# SAMV71_Xplained_Ultra_EDBG.net
KiCad netlist of a schematic drawn in Altium Designer
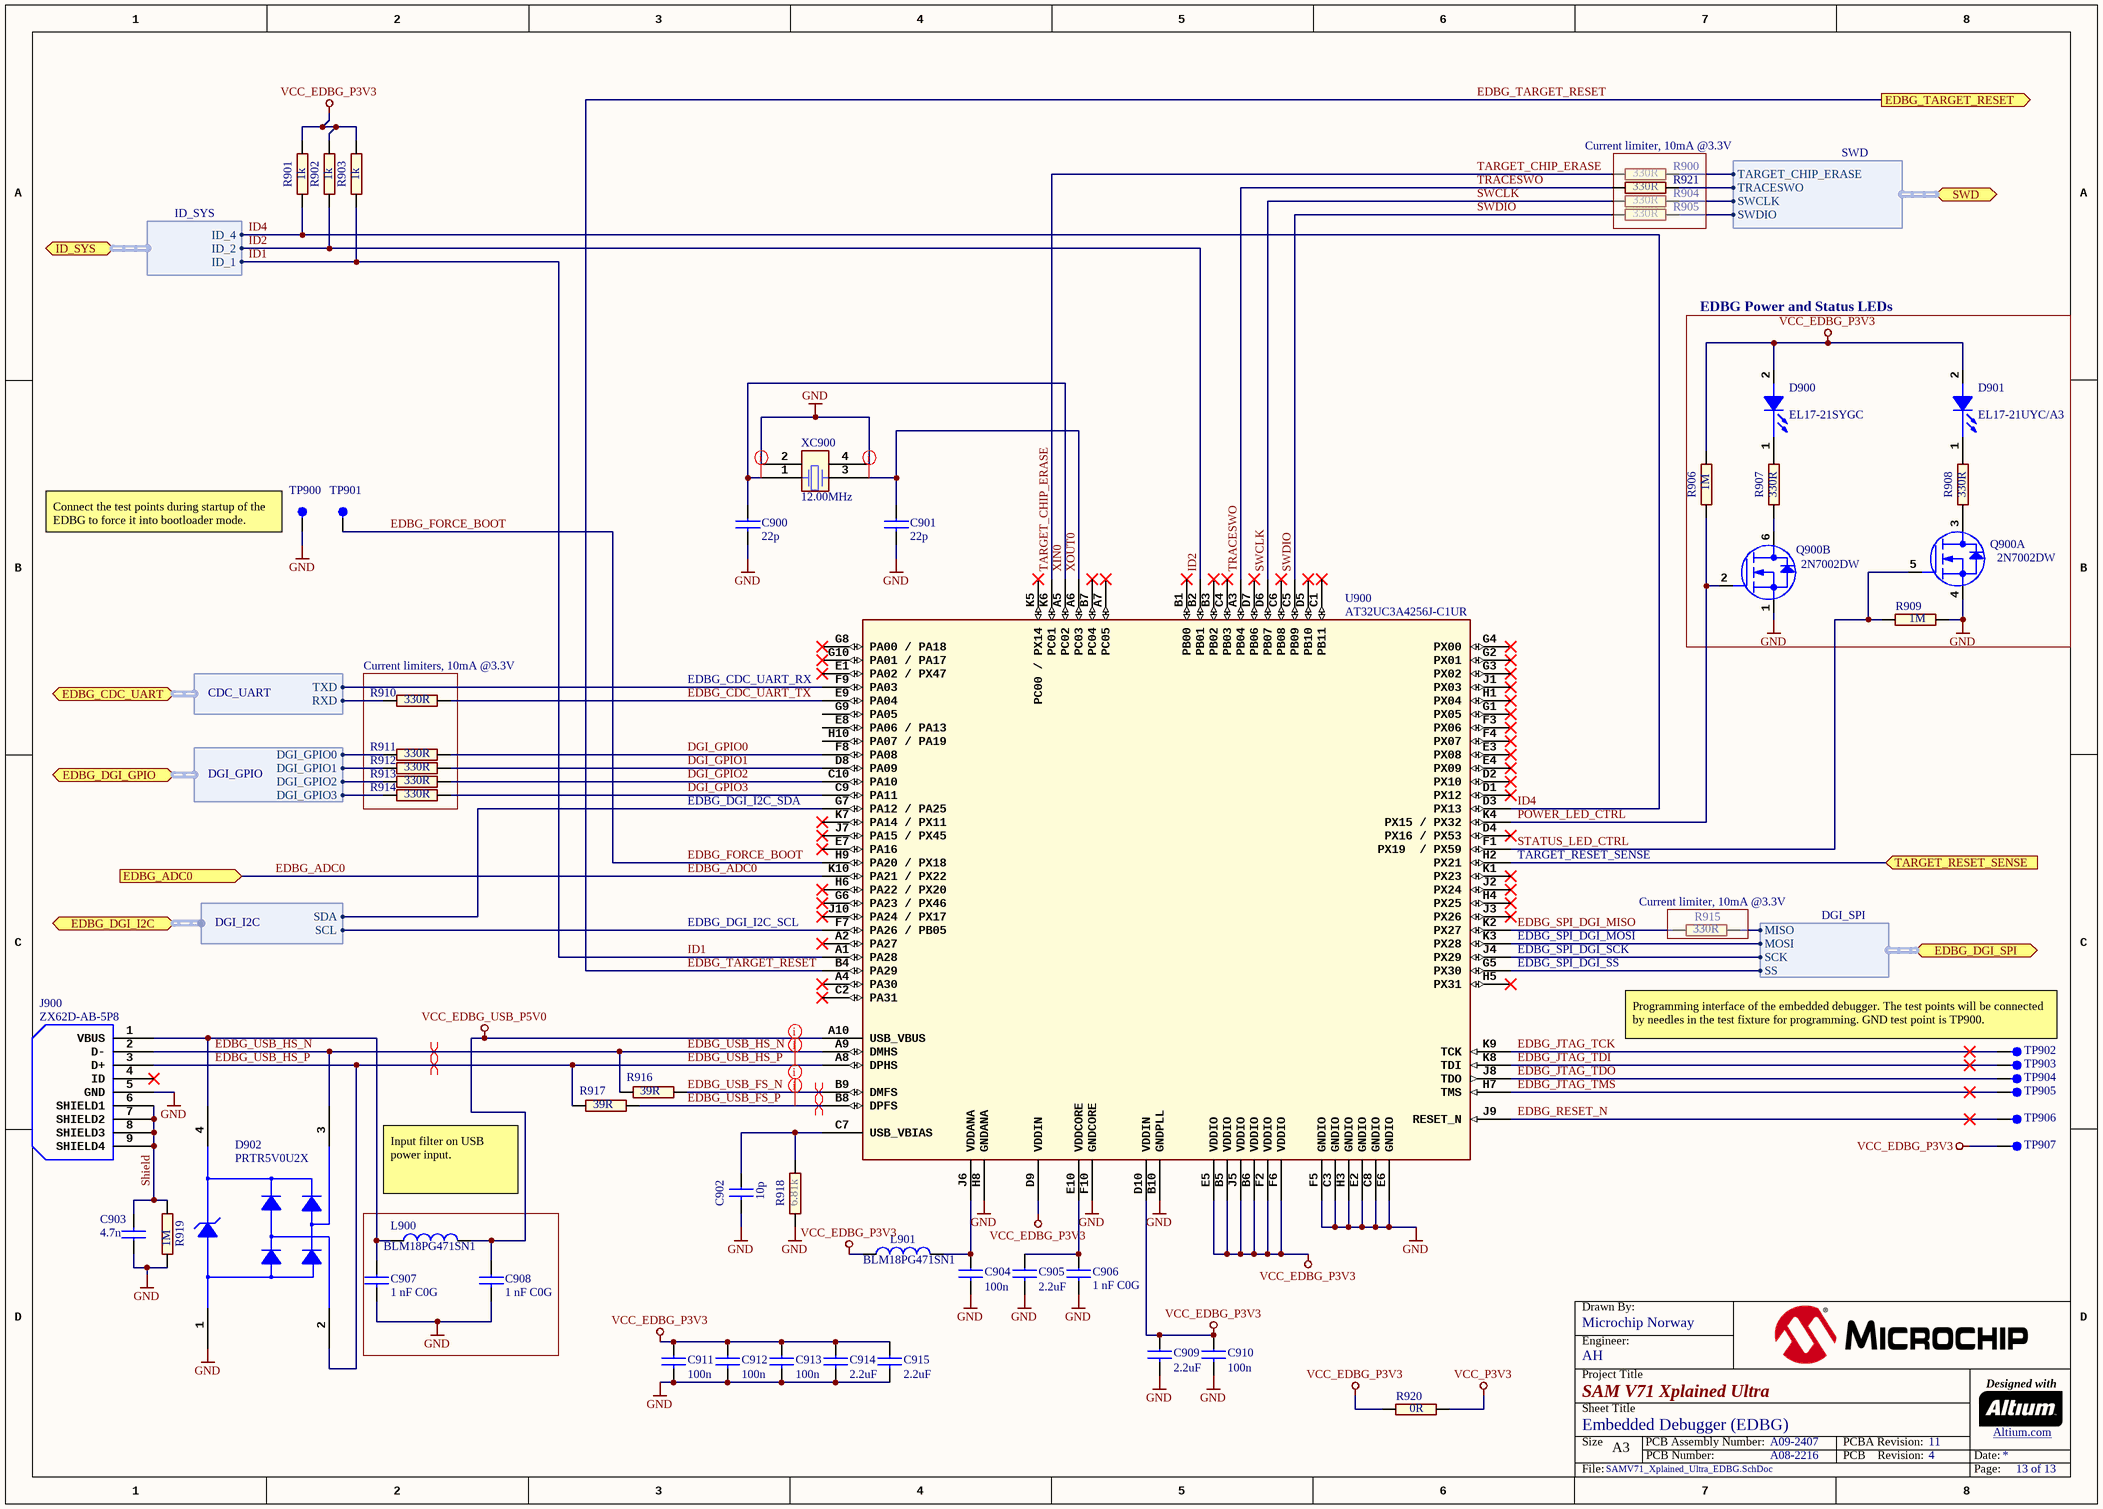
[diagram p0: SAMV71_Xplained_Ultra_EDBG.SchDoc]

(export (version "E")
  (design (tool "Eeschema 10.0.6"))
  (components
    (comp (ref "C900")
      (value "22p")
      (footprint "AP1-00053")
      (description "Ceramic capacitor, SMD 0402, NP0, 50V, +/-5%")
      (fields (field (name "TOLERANCE") "50V, +/-5%") (field (name "MANUFACTURER") "YAGEO CORP"))
      (libsource (lib "AltiumDbLib") (part "CAP-NONPOL"))
    )
    (comp (ref "C901")
      (value "22p")
      (footprint "AP1-00053")
      (description "Ceramic capacitor, SMD 0402, NP0, 50V, +/-5%")
      (fields (field (name "TOLERANCE") "50V, +/-5%") (field (name "MANUFACTURER") "YAGEO CORP"))
      (libsource (lib "AltiumDbLib") (part "CAP-NONPOL"))
    )
    (comp (ref "C902")
      (value "10p")
      (footprint "AP1-00053")
      (description "Ceramic capacitor, SMD 0402, NP0, 50V, +/-5%")
      (fields (field (name "TOLERANCE") "50V, +/-5%") (field (name "MANUFACTURER") "AVX"))
      (libsource (lib "AltiumDbLib") (part "CAP-NONPOL"))
    )
    (comp (ref "C903")
      (value "4.7n")
      (footprint "AP1-00053")
      (description "Ceramic capacitor, SMD 0402, X7R, 25V, +/-10%")
      (fields (field (name "TOLERANCE") "25V, +/-10%") (field (name "MANUFACTURER") "PHYCOMP"))
      (libsource (lib "AltiumDbLib") (part "CAP-NONPOL"))
    )
    (comp (ref "C904")
      (value "100n")
      (footprint "AP1-00053")
      (description "Ceramic capacitor, SMD 0402, X7R, 16V, +/-10%")
      (fields (field (name "TOLERANCE") "16V, +/-10%") (field (name "MANUFACTURER") "Kemet"))
      (libsource (lib "AltiumDbLib") (part "CAP-NONPOL"))
    )
    (comp (ref "C905")
      (value "2.2uF")
      (footprint "AP1-00053")
      (description "Ceramic capacitor, SMD 0402, X5R, 6.3V, +/-20%")
      (fields (field (name "TOLERANCE") "Â±20%") (field (name "MANUFACTURER") "Kemet"))
      (libsource (lib "AltiumDbLib") (part "CAP-NONPOL"))
    )
    (comp (ref "C906")
      (value "1 nF C0G")
      (footprint "AP1-00053")
      (description "Ceramic capacitor, SMD 0402, C0G, 50V, +/-5%")
      (fields (field (name "TOLERANCE") "5%") (field (name "MANUFACTURER") "Murata"))
      (libsource (lib "AltiumDbLib") (part "CAP-NONPOL"))
    )
    (comp (ref "C907")
      (value "1 nF C0G")
      (footprint "AP1-00053")
      (description "Ceramic capacitor, SMD 0402, C0G, 50V, +/-5%")
      (fields (field (name "TOLERANCE") "5%") (field (name "MANUFACTURER") "Murata"))
      (libsource (lib "AltiumDbLib") (part "CAP-NONPOL"))
    )
    (comp (ref "C908")
      (value "1 nF C0G")
      (footprint "AP1-00053")
      (description "Ceramic capacitor, SMD 0402, C0G, 50V, +/-5%")
      (fields (field (name "TOLERANCE") "5%") (field (name "MANUFACTURER") "Murata"))
      (libsource (lib "AltiumDbLib") (part "CAP-NONPOL"))
    )
    (comp (ref "C909")
      (value "2.2uF")
      (footprint "AP1-00053")
      (description "Ceramic capacitor, SMD 0402, X5R, 6.3V, +/-20%")
      (fields (field (name "TOLERANCE") "Â±20%") (field (name "MANUFACTURER") "Kemet"))
      (libsource (lib "AltiumDbLib") (part "CAP-NONPOL"))
    )
    (comp (ref "C910")
      (value "100n")
      (footprint "AP1-00053")
      (description "Ceramic capacitor, SMD 0402, X7R, 16V, +/-10%")
      (fields (field (name "TOLERANCE") "16V, +/-10%") (field (name "MANUFACTURER") "Kemet"))
      (libsource (lib "AltiumDbLib") (part "CAP-NONPOL"))
    )
    (comp (ref "C911")
      (value "100n")
      (footprint "AP1-00053")
      (description "Ceramic capacitor, SMD 0402, X7R, 16V, +/-10%")
      (fields (field (name "TOLERANCE") "16V, +/-10%") (field (name "MANUFACTURER") "Kemet"))
      (libsource (lib "AltiumDbLib") (part "CAP-NONPOL"))
    )
    (comp (ref "C912")
      (value "100n")
      (footprint "AP1-00053")
      (description "Ceramic capacitor, SMD 0402, X7R, 16V, +/-10%")
      (fields (field (name "TOLERANCE") "16V, +/-10%") (field (name "MANUFACTURER") "Kemet"))
      (libsource (lib "AltiumDbLib") (part "CAP-NONPOL"))
    )
    (comp (ref "C913")
      (value "100n")
      (footprint "AP1-00053")
      (description "Ceramic capacitor, SMD 0402, X7R, 16V, +/-10%")
      (fields (field (name "TOLERANCE") "16V, +/-10%") (field (name "MANUFACTURER") "Kemet"))
      (libsource (lib "AltiumDbLib") (part "CAP-NONPOL"))
    )
    (comp (ref "C914")
      (value "2.2uF")
      (footprint "AP1-00053")
      (description "Ceramic capacitor, SMD 0402, X5R, 6.3V, +/-20%")
      (fields (field (name "TOLERANCE") "Â±20%") (field (name "MANUFACTURER") "Kemet"))
      (libsource (lib "AltiumDbLib") (part "CAP-NONPOL"))
    )
    (comp (ref "C915")
      (value "2.2uF")
      (footprint "AP1-00053")
      (description "Ceramic capacitor, SMD 0402, X5R, 6.3V, +/-20%")
      (fields (field (name "TOLERANCE") "Â±20%") (field (name "MANUFACTURER") "Kemet"))
      (libsource (lib "AltiumDbLib") (part "CAP-NONPOL"))
    )
    (comp (ref "D900")
      (value "EL17-21SYGC")
      (footprint "AP4-00013")
      (description "LED, Green, Wave length=575nm, SMD 0805, ±70°")
      (fields (field (name "MANUFACTURER") "Everlight"))
      (libsource (lib "AltiumDbLib") (part "LED_12"))
    )
    (comp (ref "D901")
      (value "EL17-21UYC/A3")
      (footprint "AP4-00013")
      (description "LED, Yellow, Wave length=591nm, SMD 0805, ±70°")
      (fields (field (name "MANUFACTURER") "Everlight") (field (name "MPN") "17-21UYC/S530-A3/TR8"))
      (libsource (lib "AltiumDbLib") (part "LED_12"))
    )
    (comp (ref "D902")
      (value "PRTR5V0U2X")
      (footprint "AP4-00001")
      (description "Double rail-to-rail USB ESD protection diode")
      (fields (field (name "MANUFACTURER") "NXP"))
      (libsource (lib "AltiumDbLib") (part "PRTR5V0U2X"))
    )
    (comp (ref "J900")
      (value "ZX62D-AB-5P8")
      (footprint "AP8-00852")
      (description "Micro USB AB Connector, Standard SMT + DIP")
      (fields (field (name "MANUFACTURER") "HIROSE") (field (name "MPN") "ZX62D-AB-5P8(30)"))
      (libsource (lib "AltiumDbLib") (part "USB_AB"))
    )
    (comp (ref "L900")
      (value "BLM18PG471SN1")
      (footprint "AP3-00005")
      (description "SMD RF inductor 0603. Z=470Ohm (@100MHz), Max R(dc)=0.65Ohm, Max current=1A")
      (fields (field (name "MANUFACTURER") "Murata"))
      (libsource (lib "AltiumDbLib") (part "INDUCTOR"))
    )
    (comp (ref "L901")
      (value "BLM18PG471SN1")
      (footprint "AP3-00005")
      (description "SMD RF inductor 0603. Z=470Ohm (@100MHz), Max R(dc)=0.65Ohm, Max current=1A")
      (fields (field (name "MANUFACTURER") "Murata"))
      (libsource (lib "AltiumDbLib") (part "INDUCTOR"))
    )
    (comp (ref "Q900")
      (value "2N7002DW")
      (footprint "AP5-00001")
      (description "Dual N-Channel MOSFET, 60V, 115mA cont,RDS(ON) < 7.5 Ohm @50mA@5V, SOT-363")
      (fields (field (name "MANUFACTURER") "Fairchild"))
      (libsource (lib "AltiumDbLib") (part "MOSFET_DUAL_N_S2G2D1S1G1D2"))
    )
    (comp (ref "R900")
      (value "330R")
      (footprint "AP2-00000")
      (description "Thick film resistor, SMD 0402, 1/16W, 1%")
      (fields (field (name "TOLERANCE") "1 %") (field (name "MANUFACTURER") "ASJ"))
      (libsource (lib "") (part "R2_1"))
    )
    (comp (ref "R901")
      (value "1k")
      (footprint "AP2-00000")
      (description "Thick film resistor, SMD 0402, 1/16W, 1%")
      (fields (field (name "TOLERANCE") "1 %") (field (name "MANUFACTURER") "ASJ"))
      (libsource (lib "AltiumDbLib") (part "R2"))
    )
    (comp (ref "R902")
      (value "1k")
      (footprint "AP2-00000")
      (description "Thick film resistor, SMD 0402, 1/16W, 1%")
      (fields (field (name "TOLERANCE") "1 %") (field (name "MANUFACTURER") "ASJ"))
      (libsource (lib "AltiumDbLib") (part "R2"))
    )
    (comp (ref "R903")
      (value "1k")
      (footprint "AP2-00000")
      (description "Thick film resistor, SMD 0402, 1/16W, 1%")
      (fields (field (name "TOLERANCE") "1 %") (field (name "MANUFACTURER") "ASJ"))
      (libsource (lib "AltiumDbLib") (part "R2"))
    )
    (comp (ref "R904")
      (value "330R")
      (footprint "AP2-00000")
      (description "Thick film resistor, SMD 0402, 1/16W, 1%")
      (fields (field (name "TOLERANCE") "1 %") (field (name "MANUFACTURER") "ASJ"))
      (libsource (lib "") (part "R2_1"))
    )
    (comp (ref "R905")
      (value "330R")
      (footprint "AP2-00000")
      (description "Thick film resistor, SMD 0402, 1/16W, 1%")
      (fields (field (name "TOLERANCE") "1 %") (field (name "MANUFACTURER") "ASJ"))
      (libsource (lib "") (part "R2_1"))
    )
    (comp (ref "R906")
      (value "1M")
      (footprint "AP2-00000")
      (description "Thick film resistor, SMD 0402, 1/16W, 1%")
      (fields (field (name "TOLERANCE") "1 %") (field (name "MANUFACTURER") "ASJ"))
      (libsource (lib "AltiumDbLib") (part "R2"))
    )
    (comp (ref "R907")
      (value "330R")
      (footprint "AP2-00000")
      (description "Thick film resistor, SMD 0402, 1/16W, 1%")
      (fields (field (name "TOLERANCE") "1 %") (field (name "MANUFACTURER") "ASJ"))
      (libsource (lib "AltiumDbLib") (part "R2"))
    )
    (comp (ref "R908")
      (value "330R")
      (footprint "AP2-00000")
      (description "Thick film resistor, SMD 0402, 1/16W, 1%")
      (fields (field (name "TOLERANCE") "1 %") (field (name "MANUFACTURER") "ASJ"))
      (libsource (lib "AltiumDbLib") (part "R2"))
    )
    (comp (ref "R909")
      (value "1M")
      (footprint "AP2-00000")
      (description "Thick film resistor, SMD 0402, 1/16W, 1%")
      (fields (field (name "TOLERANCE") "1 %") (field (name "MANUFACTURER") "ASJ"))
      (libsource (lib "") (part "R2_3"))
    )
    (comp (ref "R910")
      (value "330R")
      (footprint "AP2-00000")
      (description "Thick film resistor, SMD 0402, 1/16W, 1%")
      (fields (field (name "TOLERANCE") "1 %") (field (name "MANUFACTURER") "ASJ"))
      (libsource (lib "") (part "R2_1"))
    )
    (comp (ref "R911")
      (value "330R")
      (footprint "AP2-00000")
      (description "Thick film resistor, SMD 0402, 1/16W, 1%")
      (fields (field (name "TOLERANCE") "1 %") (field (name "MANUFACTURER") "ASJ"))
      (libsource (lib "") (part "R2_1"))
    )
    (comp (ref "R912")
      (value "330R")
      (footprint "AP2-00000")
      (description "Thick film resistor, SMD 0402, 1/16W, 1%")
      (fields (field (name "TOLERANCE") "1 %") (field (name "MANUFACTURER") "ASJ"))
      (libsource (lib "") (part "R2_1"))
    )
    (comp (ref "R913")
      (value "330R")
      (footprint "AP2-00000")
      (description "Thick film resistor, SMD 0402, 1/16W, 1%")
      (fields (field (name "TOLERANCE") "1 %") (field (name "MANUFACTURER") "ASJ"))
      (libsource (lib "") (part "R2_1"))
    )
    (comp (ref "R914")
      (value "330R")
      (footprint "AP2-00000")
      (description "Thick film resistor, SMD 0402, 1/16W, 1%")
      (fields (field (name "TOLERANCE") "1 %") (field (name "MANUFACTURER") "ASJ"))
      (libsource (lib "") (part "R2_1"))
    )
    (comp (ref "R915")
      (value "330R")
      (footprint "AP2-00000")
      (description "Thick film resistor, SMD 0402, 1/16W, 1%")
      (fields (field (name "TOLERANCE") "1 %") (field (name "MANUFACTURER") "ASJ"))
      (libsource (lib "") (part "R2_1"))
    )
    (comp (ref "R916")
      (value "39R")
      (footprint "AP2-00011")
      (description "Thick film resistor, SMD 0402, 1/16W, 1%")
      (fields (field (name "TOLERANCE") "1 %") (field (name "MANUFACTURER") "ASJ"))
      (libsource (lib "") (part "R2_2"))
    )
    (comp (ref "R917")
      (value "39R")
      (footprint "AP2-00011")
      (description "Thick film resistor, SMD 0402, 1/16W, 1%")
      (fields (field (name "TOLERANCE") "1 %") (field (name "MANUFACTURER") "ASJ"))
      (libsource (lib "") (part "R2_2"))
    )
    (comp (ref "R918")
      (value "6.81k")
      (footprint "AP2-00011")
      (description "Thick film resistor, SMD 0402, 1/16W, 1%")
      (fields (field (name "TOLERANCE") "1%") (field (name "MANUFACTURER") "vishay"))
      (libsource (lib "AltiumDbLib") (part "R2"))
    )
    (comp (ref "R919")
      (value "1M")
      (footprint "AP2-00011")
      (description "Thick film resistor, SMD 0402, 1/16W, 1%")
      (fields (field (name "TOLERANCE") "1 %") (field (name "MANUFACTURER") "ASJ"))
      (libsource (lib "") (part "R2_4"))
    )
    (comp (ref "R920")
      (value "0R")
      (footprint "AP2-00000")
      (description "Thick film resistor, SMD 0402, 1/16W, 1%")
      (fields (field (name "TOLERANCE") "1 %") (field (name "MANUFACTURER") "(n/a)"))
      (libsource (lib "") (part "R2_1"))
    )
    (comp (ref "R921")
      (value "330R")
      (footprint "AP2-00000")
      (description "Thick film resistor, SMD 0402, 1/16W, 1%")
      (fields (field (name "TOLERANCE") "1 %") (field (name "MANUFACTURER") "ASJ"))
      (libsource (lib "") (part "R2_1"))
    )
    (comp (ref "TP900")
      (value "~")
      (footprint "AP8-00010")
      (description "Single SMD testpad")
      (libsource (lib "AltiumDbLib") (part "TESTPOINT"))
    )
    (comp (ref "TP901")
      (value "~")
      (footprint "AP8-00010")
      (description "Single SMD testpad")
      (libsource (lib "AltiumDbLib") (part "TESTPOINT"))
    )
    (comp (ref "TP902")
      (value "~")
      (footprint "AP8-00010")
      (description "Single SMD testpad")
      (libsource (lib "AltiumDbLib") (part "TESTPOINT"))
    )
    (comp (ref "TP903")
      (value "~")
      (footprint "AP8-00010")
      (description "Single SMD testpad")
      (libsource (lib "AltiumDbLib") (part "TESTPOINT"))
    )
    (comp (ref "TP904")
      (value "~")
      (footprint "AP8-00010")
      (description "Single SMD testpad")
      (libsource (lib "AltiumDbLib") (part "TESTPOINT"))
    )
    (comp (ref "TP905")
      (value "~")
      (footprint "AP8-00010")
      (description "Single SMD testpad")
      (libsource (lib "AltiumDbLib") (part "TESTPOINT"))
    )
    (comp (ref "TP906")
      (value "~")
      (footprint "AP8-00010")
      (description "Single SMD testpad")
      (libsource (lib "AltiumDbLib") (part "TESTPOINT"))
    )
    (comp (ref "TP907")
      (value "~")
      (footprint "AP8-00010")
      (description "Single SMD testpad")
      (libsource (lib "AltiumDbLib") (part "TESTPOINT"))
    )
    (comp (ref "U900")
      (value "AT32UC3A4256J-C1UR")
      (footprint "AP6-00206")
      (description "AVR 32-bit RISC MCU")
      (fields (field (name "MANUFACTURER") "ATMEL") (field (name "Comment") "100 ball VFBGA"))
      (libsource (lib "AltiumDbLib") (part "AT32UC3A4_VFBGA"))
    )
    (comp (ref "XC900")
      (value "12.00MHz")
      (footprint "AP7-00039")
      (description "Fox FQ5032B 12.0MHz SMD crystal 738B-12")
      (fields (field (name "TOLERANCE") "Â±30ppm") (field (name "MANUFACTURER") "Fox  Electronics"))
      (libsource (lib "AltiumDbLib") (part "CRYSTAL1324"))
    )
  )
  (nets
    (net (code "7") (name "/DGI_GPIO0") (class "Default")
      (node (ref "R911") (pin "2") (pinfunction "2_2") (pintype "passive"))
      (node (ref "U900") (pin "F8") (pinfunction "PA08_F8") (pintype "bidirectional"))
    )
    (net (code "8") (name "/DGI_GPIO1") (class "Default")
      (node (ref "R912") (pin "2") (pinfunction "2_2") (pintype "passive"))
      (node (ref "U900") (pin "D8") (pinfunction "PA09_D8") (pintype "bidirectional"))
    )
    (net (code "9") (name "/DGI_GPIO2") (class "Default")
      (node (ref "R913") (pin "2") (pinfunction "2_2") (pintype "passive"))
      (node (ref "U900") (pin "C10") (pinfunction "PA10_C10") (pintype "bidirectional"))
    )
    (net (code "10") (name "/DGI_GPIO3") (class "Default")
      (node (ref "R914") (pin "2") (pinfunction "2_2") (pintype "passive"))
      (node (ref "U900") (pin "C9") (pinfunction "PA11_C9") (pintype "bidirectional"))
    )
    (net (code "11") (name "/EDBG_ADC0") (class "Default")
      (node (ref "U900") (pin "K10") (pinfunction "PA21_/_PX22_K10") (pintype "bidirectional"))
    )
    (net (code "12") (name "/EDBG_CDC_UART_TX") (class "Default")
      (node (ref "R910") (pin "2") (pinfunction "2_2") (pintype "passive"))
      (node (ref "U900") (pin "E9") (pinfunction "PA04_E9") (pintype "bidirectional"))
    )
    (net (code "13") (name "/EDBG_FORCE_BOOT") (class "Default")
      (node (ref "TP901") (pin "1") (pinfunction "1_1") (pintype "passive"))
      (node (ref "U900") (pin "H9") (pinfunction "PA20_/_PX18_H9") (pintype "bidirectional"))
    )
    (net (code "14") (name "/EDBG_JTAG_TCK") (class "Default")
      (node (ref "TP902") (pin "1") (pinfunction "1_1") (pintype "passive"))
      (node (ref "U900") (pin "K9") (pinfunction "TCK_K9") (pintype "input"))
    )
    (net (code "15") (name "/EDBG_JTAG_TDI") (class "Default")
      (node (ref "TP903") (pin "1") (pinfunction "1_1") (pintype "passive"))
      (node (ref "U900") (pin "K8") (pinfunction "TDI_K8") (pintype "input"))
    )
    (net (code "16") (name "/EDBG_JTAG_TDO") (class "Default")
      (node (ref "TP904") (pin "1") (pinfunction "1_1") (pintype "passive"))
      (node (ref "U900") (pin "J8") (pinfunction "TDO_J8") (pintype "output"))
    )
    (net (code "17") (name "/EDBG_JTAG_TMS") (class "Default")
      (node (ref "TP905") (pin "1") (pinfunction "1_1") (pintype "passive"))
      (node (ref "U900") (pin "H7") (pinfunction "TMS_H7") (pintype "input"))
    )
    (net (code "18") (name "/EDBG_RESET_N") (class "Default")
      (node (ref "TP906") (pin "1") (pinfunction "1_1") (pintype "passive"))
      (node (ref "U900") (pin "J9") (pinfunction "RESET_N_J9") (pintype "input"))
    )
    (net (code "19") (name "/EDBG_SPI_DGI_MISO") (class "Default")
      (node (ref "R915") (pin "1") (pinfunction "1_1") (pintype "passive"))
      (node (ref "U900") (pin "K2") (pinfunction "PX27_K2") (pintype "bidirectional"))
    )
    (net (code "20") (name "/EDBG_TARGET_RESET") (class "Default")
      (node (ref "U900") (pin "B4") (pinfunction "PA29_B4") (pintype "bidirectional"))
    )
    (net (code "21") (name "/EDBG_USB_FS_N") (class "Default")
      (node (ref "R916") (pin "2") (pinfunction "2_2") (pintype "passive"))
      (node (ref "U900") (pin "B9") (pinfunction "DMFS_B9") (pintype "bidirectional"))
    )
    (net (code "22") (name "/EDBG_USB_FS_P") (class "Default")
      (node (ref "R917") (pin "2") (pinfunction "2_2") (pintype "passive"))
      (node (ref "U900") (pin "B8") (pinfunction "DPFS_B8") (pintype "bidirectional"))
    )
    (net (code "23") (name "/EDBG_USB_HS_N") (class "Default")
      (node (ref "D902") (pin "3") (pinfunction "I/O_2_3") (pintype "passive"))
      (node (ref "J900") (pin "2") (pinfunction "D-_2") (pintype "passive"))
      (node (ref "R916") (pin "1") (pinfunction "1_1") (pintype "passive"))
      (node (ref "U900") (pin "A9") (pinfunction "DMHS_A9") (pintype "bidirectional"))
    )
    (net (code "24") (name "/EDBG_USB_HS_P") (class "Default")
      (node (ref "D902") (pin "2") (pinfunction "I/O_1_2") (pintype "passive"))
      (node (ref "J900") (pin "3") (pinfunction "D+_3") (pintype "passive"))
      (node (ref "R917") (pin "1") (pinfunction "1_1") (pintype "passive"))
      (node (ref "U900") (pin "A8") (pinfunction "DPHS_A8") (pintype "bidirectional"))
    )
    (net (code "25") (name "/ID1") (class "Default")
      (node (ref "R903") (pin "1") (pinfunction "1_1") (pintype "passive"))
      (node (ref "U900") (pin "A1") (pinfunction "PA28_A1") (pintype "bidirectional"))
    )
    (net (code "26") (name "/ID2") (class "Default")
      (node (ref "R902") (pin "1") (pinfunction "1_1") (pintype "passive"))
      (node (ref "U900") (pin "B2") (pinfunction "PB01_B2") (pintype "bidirectional"))
    )
    (net (code "27") (name "/ID4") (class "Default")
      (node (ref "R901") (pin "1") (pinfunction "1_1") (pintype "passive"))
      (node (ref "U900") (pin "D3") (pinfunction "PX13_D3") (pintype "bidirectional"))
    )
    (net (code "28") (name "/MISO") (class "Default")
      (node (ref "R915") (pin "2") (pinfunction "2_2") (pintype "passive"))
    )
    (net (code "29") (name "/MOSI") (class "Default")
      (node (ref "U900") (pin "K3") (pinfunction "PX28_K3") (pintype "bidirectional"))
    )
    (net (code "30") (name "/POWER_LED_CTRL") (class "Default")
      (node (ref "Q900") (pin "2") (pinfunction "G2_2") (pintype "passive"))
      (node (ref "R906") (pin "1") (pinfunction "1_1") (pintype "passive"))
      (node (ref "U900") (pin "K4") (pinfunction "PX15_/_PX32_K4") (pintype "bidirectional"))
    )
    (net (code "31") (name "/RXD") (class "Default")
      (node (ref "R910") (pin "1") (pinfunction "1_1") (pintype "passive"))
    )
    (net (code "32") (name "/SCK") (class "Default")
      (node (ref "U900") (pin "J4") (pinfunction "PX29_J4") (pintype "bidirectional"))
    )
    (net (code "33") (name "/SCL") (class "Default")
      (node (ref "U900") (pin "F7") (pinfunction "PA26_/_PB05_F7") (pintype "bidirectional"))
    )
    (net (code "34") (name "/SDA") (class "Default")
      (node (ref "U900") (pin "G7") (pinfunction "PA12_/_PA25_G7") (pintype "bidirectional"))
    )
    (net (code "35") (name "/SS") (class "Default")
      (node (ref "U900") (pin "G5") (pinfunction "PX30_G5") (pintype "bidirectional"))
    )
    (net (code "36") (name "/STATUS_LED_CTRL") (class "Default")
      (node (ref "Q900") (pin "5") (pinfunction "G1_5") (pintype "passive"))
      (node (ref "R909") (pin "2") (pinfunction "2_2") (pintype "passive"))
      (node (ref "U900") (pin "F1") (pinfunction "PX19__/_PX59_F1") (pintype "bidirectional"))
    )
    (net (code "37") (name "/SWCLK") (class "Default")
      (node (ref "R904") (pin "1") (pinfunction "1_1") (pintype "passive"))
      (node (ref "U900") (pin "D6") (pinfunction "PB07_D6") (pintype "bidirectional"))
    )
    (net (code "38") (name "/SWDIO") (class "Default")
      (node (ref "R905") (pin "1") (pinfunction "1_1") (pintype "passive"))
      (node (ref "U900") (pin "C5") (pinfunction "PB09_C5") (pintype "bidirectional"))
    )
    (net (code "39") (name "/Shield") (class "Default")
      (node (ref "C903") (pin "2") (pinfunction "2_2") (pintype "passive"))
      (node (ref "J900") (pin "6") (pinfunction "SHIELD1_6") (pintype "passive"))
      (node (ref "J900") (pin "7") (pinfunction "SHIELD2_7") (pintype "passive"))
      (node (ref "J900") (pin "8") (pinfunction "SHIELD3_8") (pintype "passive"))
      (node (ref "J900") (pin "9") (pinfunction "SHIELD4_9") (pintype "passive"))
      (node (ref "R919") (pin "2") (pinfunction "2_2") (pintype "passive"))
    )
    (net (code "40") (name "/TARGET_CHIP_ERASE") (class "Default")
      (node (ref "R900") (pin "1") (pinfunction "1_1") (pintype "passive"))
      (node (ref "U900") (pin "K6") (pinfunction "PC01_K6") (pintype "bidirectional"))
    )
    (net (code "41") (name "/TARGET_RESET_SENSE") (class "Default")
      (node (ref "U900") (pin "H2") (pinfunction "PX21_H2") (pintype "bidirectional"))
    )
    (net (code "42") (name "/TRACESWO") (class "Default")
      (node (ref "R921") (pin "1") (pinfunction "1_1") (pintype "passive"))
      (node (ref "U900") (pin "A3") (pinfunction "PB04_A3") (pintype "bidirectional"))
    )
    (net (code "43") (name "/TXD") (class "Default")
      (node (ref "U900") (pin "F9") (pinfunction "PA03_F9") (pintype "bidirectional"))
    )
    (net (code "44") (name "/XIN0") (class "Default")
      (node (ref "C900") (pin "1") (pinfunction "1_1") (pintype "passive"))
      (node (ref "U900") (pin "A5") (pinfunction "PC02_A5") (pintype "bidirectional"))
      (node (ref "XC900") (pin "1") (pinfunction "1_1") (pintype "passive"))
    )
    (net (code "45") (name "/XOUT0") (class "Default")
      (node (ref "C901") (pin "1") (pinfunction "1_1") (pintype "passive"))
      (node (ref "U900") (pin "A6") (pinfunction "PC03_A6") (pintype "bidirectional"))
      (node (ref "XC900") (pin "3") (pinfunction "3_3") (pintype "passive"))
    )
    (net (code "52") (name "GND") (class "Default")
      (node (ref "C900") (pin "2") (pinfunction "2_2") (pintype "passive"))
      (node (ref "C901") (pin "2") (pinfunction "2_2") (pintype "passive"))
      (node (ref "C902") (pin "2") (pinfunction "2_2") (pintype "passive"))
      (node (ref "C903") (pin "1") (pinfunction "1_1") (pintype "passive"))
      (node (ref "C904") (pin "2") (pinfunction "2_2") (pintype "passive"))
      (node (ref "C905") (pin "2") (pinfunction "2_2") (pintype "passive"))
      (node (ref "C906") (pin "2") (pinfunction "2_2") (pintype "passive"))
      (node (ref "C907") (pin "2") (pinfunction "2_2") (pintype "passive"))
      (node (ref "C908") (pin "2") (pinfunction "2_2") (pintype "passive"))
      (node (ref "C909") (pin "2") (pinfunction "2_2") (pintype "passive"))
      (node (ref "C910") (pin "2") (pinfunction "2_2") (pintype "passive"))
      (node (ref "C911") (pin "2") (pinfunction "2_2") (pintype "passive"))
      (node (ref "C912") (pin "2") (pinfunction "2_2") (pintype "passive"))
      (node (ref "C913") (pin "2") (pinfunction "2_2") (pintype "passive"))
      (node (ref "C914") (pin "2") (pinfunction "2_2") (pintype "passive"))
      (node (ref "C915") (pin "2") (pinfunction "2_2") (pintype "passive"))
      (node (ref "D902") (pin "1") (pinfunction "GND_1") (pintype "passive"))
      (node (ref "J900") (pin "5") (pinfunction "GND_5") (pintype "passive"))
      (node (ref "Q900") (pin "1") (pinfunction "S2_1") (pintype "passive"))
      (node (ref "Q900") (pin "4") (pinfunction "S1_4") (pintype "passive"))
      (node (ref "R909") (pin "1") (pinfunction "1_1") (pintype "passive"))
      (node (ref "R918") (pin "1") (pinfunction "1_1") (pintype "passive"))
      (node (ref "R919") (pin "1") (pinfunction "1_1") (pintype "passive"))
      (node (ref "TP900") (pin "1") (pinfunction "1_1") (pintype "passive"))
      (node (ref "U900") (pin "B10") (pinfunction "GNDPLL_B10") (pintype "power_in"))
      (node (ref "U900") (pin "C3") (pinfunction "GNDIO_C3") (pintype "power_in"))
      (node (ref "U900") (pin "C8") (pinfunction "GNDIO_C8") (pintype "power_in"))
      (node (ref "U900") (pin "E2") (pinfunction "GNDIO_E2") (pintype "power_in"))
      (node (ref "U900") (pin "E6") (pinfunction "GNDIO_E6") (pintype "power_in"))
      (node (ref "U900") (pin "F10") (pinfunction "GNDCORE_F10") (pintype "power_in"))
      (node (ref "U900") (pin "F5") (pinfunction "GNDIO_F5") (pintype "power_in"))
      (node (ref "U900") (pin "H3") (pinfunction "GNDIO_H3") (pintype "power_in"))
      (node (ref "U900") (pin "H8") (pinfunction "GNDANA_H8") (pintype "power_in"))
      (node (ref "XC900") (pin "2") (pinfunction "2_2") (pintype "passive"))
      (node (ref "XC900") (pin "4") (pinfunction "4_4") (pintype "passive"))
    )
    (net (code "53") (name "Net-(D900-CATHODE)") (class "Default")
      (node (ref "D900") (pin "1") (pinfunction "CATHODE_1") (pintype "passive"))
      (node (ref "R907") (pin "2") (pinfunction "2_2") (pintype "passive"))
    )
    (net (code "54") (name "Net-(D901-CATHODE)") (class "Default")
      (node (ref "D901") (pin "1") (pinfunction "CATHODE_1") (pintype "passive"))
      (node (ref "R908") (pin "2") (pinfunction "2_2") (pintype "passive"))
    )
    (net (code "55") (name "Net-(D902-VCC)") (class "Default")
      (node (ref "C907") (pin "1") (pinfunction "1_1") (pintype "passive"))
      (node (ref "D902") (pin "4") (pinfunction "VCC_4") (pintype "passive"))
      (node (ref "J900") (pin "1") (pinfunction "VBUS_1") (pintype "passive"))
      (node (ref "L900") (pin "1") (pinfunction "1_1") (pintype "passive"))
    )
    (net (code "56") (name "Net-(Q900A-D1)") (class "Default")
      (node (ref "Q900") (pin "3") (pinfunction "D1_3") (pintype "passive"))
      (node (ref "R908") (pin "1") (pinfunction "1_1") (pintype "passive"))
    )
    (net (code "57") (name "Net-(Q900B-D2)") (class "Default")
      (node (ref "Q900") (pin "6") (pinfunction "D2_6") (pintype "passive"))
      (node (ref "R907") (pin "1") (pinfunction "1_1") (pintype "passive"))
    )
    (net (code "58") (name "Net-(U900-USB_VBIAS)") (class "Default")
      (node (ref "C902") (pin "1") (pinfunction "1_1") (pintype "passive"))
      (node (ref "R918") (pin "2") (pinfunction "2_2") (pintype "passive"))
      (node (ref "U900") (pin "C7") (pinfunction "USB_VBIAS_C7") (pintype "power_in"))
    )
    (net (code "59") (name "Net-(U900-VDDANA)") (class "Default")
      (node (ref "C904") (pin "1") (pinfunction "1_1") (pintype "passive"))
      (node (ref "L901") (pin "2") (pinfunction "2_2") (pintype "passive"))
      (node (ref "U900") (pin "J6") (pinfunction "VDDANA_J6") (pintype "power_in"))
    )
    (net (code "60") (name "Net-(U900-VDDCORE)") (class "Default")
      (node (ref "C905") (pin "1") (pinfunction "1_1") (pintype "passive"))
      (node (ref "C906") (pin "1") (pinfunction "1_1") (pintype "passive"))
      (node (ref "U900") (pin "E10") (pinfunction "VDDCORE_E10") (pintype "power_in"))
    )
    (net (code "61") (name "VCC_EDBG_P3V3") (class "Default")
      (node (ref "C909") (pin "1") (pinfunction "1_1") (pintype "passive"))
      (node (ref "C910") (pin "1") (pinfunction "1_1") (pintype "passive"))
      (node (ref "C911") (pin "1") (pinfunction "1_1") (pintype "passive"))
      (node (ref "C912") (pin "1") (pinfunction "1_1") (pintype "passive"))
      (node (ref "C913") (pin "1") (pinfunction "1_1") (pintype "passive"))
      (node (ref "C914") (pin "1") (pinfunction "1_1") (pintype "passive"))
      (node (ref "C915") (pin "1") (pinfunction "1_1") (pintype "passive"))
      (node (ref "D900") (pin "2") (pinfunction "ANODE_2") (pintype "passive"))
      (node (ref "D901") (pin "2") (pinfunction "ANODE_2") (pintype "passive"))
      (node (ref "L901") (pin "1") (pinfunction "1_1") (pintype "passive"))
      (node (ref "R901") (pin "2") (pinfunction "2_2") (pintype "passive"))
      (node (ref "R902") (pin "2") (pinfunction "2_2") (pintype "passive"))
      (node (ref "R903") (pin "2") (pinfunction "2_2") (pintype "passive"))
      (node (ref "R906") (pin "2") (pinfunction "2_2") (pintype "passive"))
      (node (ref "R920") (pin "1") (pinfunction "1_1") (pintype "passive"))
      (node (ref "TP907") (pin "1") (pinfunction "1_1") (pintype "passive"))
      (node (ref "U900") (pin "B5") (pinfunction "VDDIO_B5") (pintype "power_in"))
      (node (ref "U900") (pin "B6") (pinfunction "VDDIO_B6") (pintype "power_in"))
      (node (ref "U900") (pin "D10") (pinfunction "VDDIN_D10") (pintype "power_in"))
      (node (ref "U900") (pin "D9") (pinfunction "VDDIN_D9") (pintype "power_in"))
      (node (ref "U900") (pin "E5") (pinfunction "VDDIO_E5") (pintype "power_in"))
      (node (ref "U900") (pin "F2") (pinfunction "VDDIO_F2") (pintype "power_in"))
      (node (ref "U900") (pin "F6") (pinfunction "VDDIO_F6") (pintype "power_in"))
      (node (ref "U900") (pin "J5") (pinfunction "VDDIO_J5") (pintype "power_in"))
    )
    (net (code "62") (name "VCC_EDBG_USB_P5V0") (class "Default")
      (node (ref "C908") (pin "1") (pinfunction "1_1") (pintype "passive"))
      (node (ref "L900") (pin "2") (pinfunction "2_2") (pintype "passive"))
      (node (ref "U900") (pin "A10") (pinfunction "USB_VBUS_A10") (pintype "power_in"))
    )
    (net (code "63") (name "VCC_P3V3") (class "Default")
      (node (ref "R920") (pin "2") (pinfunction "2_2") (pintype "passive"))
    )
    (net (code "64") (name "unconnected-(J900-ID-Pad4)") (class "Default")
      (node (ref "J900") (pin "4") (pinfunction "ID_4") (pintype "passive+no_connect"))
    )
    (net (code "65") (name "unconnected-(R900-Pad2)") (class "Default")
      (node (ref "R900") (pin "2") (pinfunction "2_2") (pintype "passive"))
    )
    (net (code "66") (name "unconnected-(R904-Pad2)") (class "Default")
      (node (ref "R904") (pin "2") (pinfunction "2_2") (pintype "passive"))
    )
    (net (code "67") (name "unconnected-(R905-Pad2)") (class "Default")
      (node (ref "R905") (pin "2") (pinfunction "2_2") (pintype "passive"))
    )
    (net (code "68") (name "unconnected-(R911-Pad1)") (class "Default")
      (node (ref "R911") (pin "1") (pinfunction "1_1") (pintype "passive"))
    )
    (net (code "69") (name "unconnected-(R912-Pad1)") (class "Default")
      (node (ref "R912") (pin "1") (pinfunction "1_1") (pintype "passive"))
    )
    (net (code "70") (name "unconnected-(R913-Pad1)") (class "Default")
      (node (ref "R913") (pin "1") (pinfunction "1_1") (pintype "passive"))
    )
    (net (code "71") (name "unconnected-(R914-Pad1)") (class "Default")
      (node (ref "R914") (pin "1") (pinfunction "1_1") (pintype "passive"))
    )
    (net (code "72") (name "unconnected-(R921-Pad2)") (class "Default")
      (node (ref "R921") (pin "2") (pinfunction "2_2") (pintype "passive"))
    )
    (net (code "73") (name "unconnected-(U900-PA00_{slash}_PA18-PadG8)") (class "Default")
      (node (ref "U900") (pin "G8") (pinfunction "PA00_/_PA18_G8") (pintype "bidirectional+no_connect"))
    )
    (net (code "74") (name "unconnected-(U900-PA01_{slash}_PA17-PadG10)") (class "Default")
      (node (ref "U900") (pin "G10") (pinfunction "PA01_/_PA17_G10") (pintype "bidirectional+no_connect"))
    )
    (net (code "75") (name "unconnected-(U900-PA02_{slash}_PX47-PadE1)") (class "Default")
      (node (ref "U900") (pin "E1") (pinfunction "PA02_/_PX47_E1") (pintype "bidirectional+no_connect"))
    )
    (net (code "76") (name "unconnected-(U900-PA05-PadG9)") (class "Default")
      (node (ref "U900") (pin "G9") (pinfunction "PA05_G9") (pintype "bidirectional"))
    )
    (net (code "77") (name "unconnected-(U900-PA06_{slash}_PA13-PadE8)") (class "Default")
      (node (ref "U900") (pin "E8") (pinfunction "PA06_/_PA13_E8") (pintype "bidirectional"))
    )
    (net (code "78") (name "unconnected-(U900-PA07_{slash}_PA19-PadH10)") (class "Default")
      (node (ref "U900") (pin "H10") (pinfunction "PA07_/_PA19_H10") (pintype "bidirectional"))
    )
    (net (code "79") (name "unconnected-(U900-PA14_{slash}_PX11-PadK7)") (class "Default")
      (node (ref "U900") (pin "K7") (pinfunction "PA14_/_PX11_K7") (pintype "bidirectional+no_connect"))
    )
    (net (code "80") (name "unconnected-(U900-PA15_{slash}_PX45-PadJ7)") (class "Default")
      (node (ref "U900") (pin "J7") (pinfunction "PA15_/_PX45_J7") (pintype "bidirectional+no_connect"))
    )
    (net (code "81") (name "unconnected-(U900-PA16-PadE7)") (class "Default")
      (node (ref "U900") (pin "E7") (pinfunction "PA16_E7") (pintype "bidirectional+no_connect"))
    )
    (net (code "82") (name "unconnected-(U900-PA22_{slash}_PX20-PadH6)") (class "Default")
      (node (ref "U900") (pin "H6") (pinfunction "PA22_/_PX20_H6") (pintype "bidirectional+no_connect"))
    )
    (net (code "83") (name "unconnected-(U900-PA23_{slash}_PX46-PadG6)") (class "Default")
      (node (ref "U900") (pin "G6") (pinfunction "PA23_/_PX46_G6") (pintype "bidirectional+no_connect"))
    )
    (net (code "84") (name "unconnected-(U900-PA24_{slash}_PX17-PadJ10)") (class "Default")
      (node (ref "U900") (pin "J10") (pinfunction "PA24_/_PX17_J10") (pintype "bidirectional+no_connect"))
    )
    (net (code "85") (name "unconnected-(U900-PA27-PadA2)") (class "Default")
      (node (ref "U900") (pin "A2") (pinfunction "PA27_A2") (pintype "bidirectional+no_connect"))
    )
    (net (code "86") (name "unconnected-(U900-PA30-PadA4)") (class "Default")
      (node (ref "U900") (pin "A4") (pinfunction "PA30_A4") (pintype "bidirectional+no_connect"))
    )
    (net (code "87") (name "unconnected-(U900-PA31-PadC2)") (class "Default")
      (node (ref "U900") (pin "C2") (pinfunction "PA31_C2") (pintype "bidirectional+no_connect"))
    )
    (net (code "88") (name "unconnected-(U900-PB00-PadB1)") (class "Default")
      (node (ref "U900") (pin "B1") (pinfunction "PB00_B1") (pintype "bidirectional+no_connect"))
    )
    (net (code "89") (name "unconnected-(U900-PB02-PadB3)") (class "Default")
      (node (ref "U900") (pin "B3") (pinfunction "PB02_B3") (pintype "bidirectional+no_connect"))
    )
    (net (code "90") (name "unconnected-(U900-PB03-PadC4)") (class "Default")
      (node (ref "U900") (pin "C4") (pinfunction "PB03_C4") (pintype "bidirectional+no_connect"))
    )
    (net (code "91") (name "unconnected-(U900-PB06-PadD7)") (class "Default")
      (node (ref "U900") (pin "D7") (pinfunction "PB06_D7") (pintype "bidirectional+no_connect"))
    )
    (net (code "92") (name "unconnected-(U900-PB08-PadC6)") (class "Default")
      (node (ref "U900") (pin "C6") (pinfunction "PB08_C6") (pintype "bidirectional+no_connect"))
    )
    (net (code "93") (name "unconnected-(U900-PB10-PadD5)") (class "Default")
      (node (ref "U900") (pin "D5") (pinfunction "PB10_D5") (pintype "bidirectional+no_connect"))
    )
    (net (code "94") (name "unconnected-(U900-PB11-PadC1)") (class "Default")
      (node (ref "U900") (pin "C1") (pinfunction "PB11_C1") (pintype "bidirectional+no_connect"))
    )
    (net (code "95") (name "unconnected-(U900-PC00_{slash}_PX14-PadK5)") (class "Default")
      (node (ref "U900") (pin "K5") (pinfunction "PC00_/_PX14_K5") (pintype "bidirectional+no_connect"))
    )
    (net (code "96") (name "unconnected-(U900-PC04-PadB7)") (class "Default")
      (node (ref "U900") (pin "B7") (pinfunction "PC04_B7") (pintype "bidirectional+no_connect"))
    )
    (net (code "97") (name "unconnected-(U900-PC05-PadA7)") (class "Default")
      (node (ref "U900") (pin "A7") (pinfunction "PC05_A7") (pintype "bidirectional+no_connect"))
    )
    (net (code "98") (name "unconnected-(U900-PX00-PadG4)") (class "Default")
      (node (ref "U900") (pin "G4") (pinfunction "PX00_G4") (pintype "bidirectional+no_connect"))
    )
    (net (code "99") (name "unconnected-(U900-PX01-PadG2)") (class "Default")
      (node (ref "U900") (pin "G2") (pinfunction "PX01_G2") (pintype "bidirectional+no_connect"))
    )
    (net (code "100") (name "unconnected-(U900-PX02-PadG3)") (class "Default")
      (node (ref "U900") (pin "G3") (pinfunction "PX02_G3") (pintype "bidirectional+no_connect"))
    )
    (net (code "101") (name "unconnected-(U900-PX03-PadJ1)") (class "Default")
      (node (ref "U900") (pin "J1") (pinfunction "PX03_J1") (pintype "bidirectional+no_connect"))
    )
    (net (code "102") (name "unconnected-(U900-PX04-PadH1)") (class "Default")
      (node (ref "U900") (pin "H1") (pinfunction "PX04_H1") (pintype "bidirectional+no_connect"))
    )
    (net (code "103") (name "unconnected-(U900-PX05-PadG1)") (class "Default")
      (node (ref "U900") (pin "G1") (pinfunction "PX05_G1") (pintype "bidirectional+no_connect"))
    )
    (net (code "104") (name "unconnected-(U900-PX06-PadF3)") (class "Default")
      (node (ref "U900") (pin "F3") (pinfunction "PX06_F3") (pintype "bidirectional+no_connect"))
    )
    (net (code "105") (name "unconnected-(U900-PX07-PadF4)") (class "Default")
      (node (ref "U900") (pin "F4") (pinfunction "PX07_F4") (pintype "bidirectional+no_connect"))
    )
    (net (code "106") (name "unconnected-(U900-PX08-PadE3)") (class "Default")
      (node (ref "U900") (pin "E3") (pinfunction "PX08_E3") (pintype "bidirectional+no_connect"))
    )
    (net (code "107") (name "unconnected-(U900-PX09-PadE4)") (class "Default")
      (node (ref "U900") (pin "E4") (pinfunction "PX09_E4") (pintype "bidirectional+no_connect"))
    )
    (net (code "108") (name "unconnected-(U900-PX10-PadD2)") (class "Default")
      (node (ref "U900") (pin "D2") (pinfunction "PX10_D2") (pintype "bidirectional+no_connect"))
    )
    (net (code "109") (name "unconnected-(U900-PX12-PadD1)") (class "Default")
      (node (ref "U900") (pin "D1") (pinfunction "PX12_D1") (pintype "bidirectional+no_connect"))
    )
    (net (code "110") (name "unconnected-(U900-PX16_{slash}_PX53-PadD4)") (class "Default")
      (node (ref "U900") (pin "D4") (pinfunction "PX16_/_PX53_D4") (pintype "bidirectional+no_connect"))
    )
    (net (code "111") (name "unconnected-(U900-PX23-PadK1)") (class "Default")
      (node (ref "U900") (pin "K1") (pinfunction "PX23_K1") (pintype "bidirectional+no_connect"))
    )
    (net (code "112") (name "unconnected-(U900-PX24-PadJ2)") (class "Default")
      (node (ref "U900") (pin "J2") (pinfunction "PX24_J2") (pintype "bidirectional+no_connect"))
    )
    (net (code "113") (name "unconnected-(U900-PX25-PadH4)") (class "Default")
      (node (ref "U900") (pin "H4") (pinfunction "PX25_H4") (pintype "bidirectional+no_connect"))
    )
    (net (code "114") (name "unconnected-(U900-PX26-PadJ3)") (class "Default")
      (node (ref "U900") (pin "J3") (pinfunction "PX26_J3") (pintype "bidirectional+no_connect"))
    )
    (net (code "115") (name "unconnected-(U900-PX31-PadH5)") (class "Default")
      (node (ref "U900") (pin "H5") (pinfunction "PX31_H5") (pintype "bidirectional+no_connect"))
    )
  )
)
